# SCH_Driver_RL.net
KiCad netlist of a schematic drawn in Altium Designer
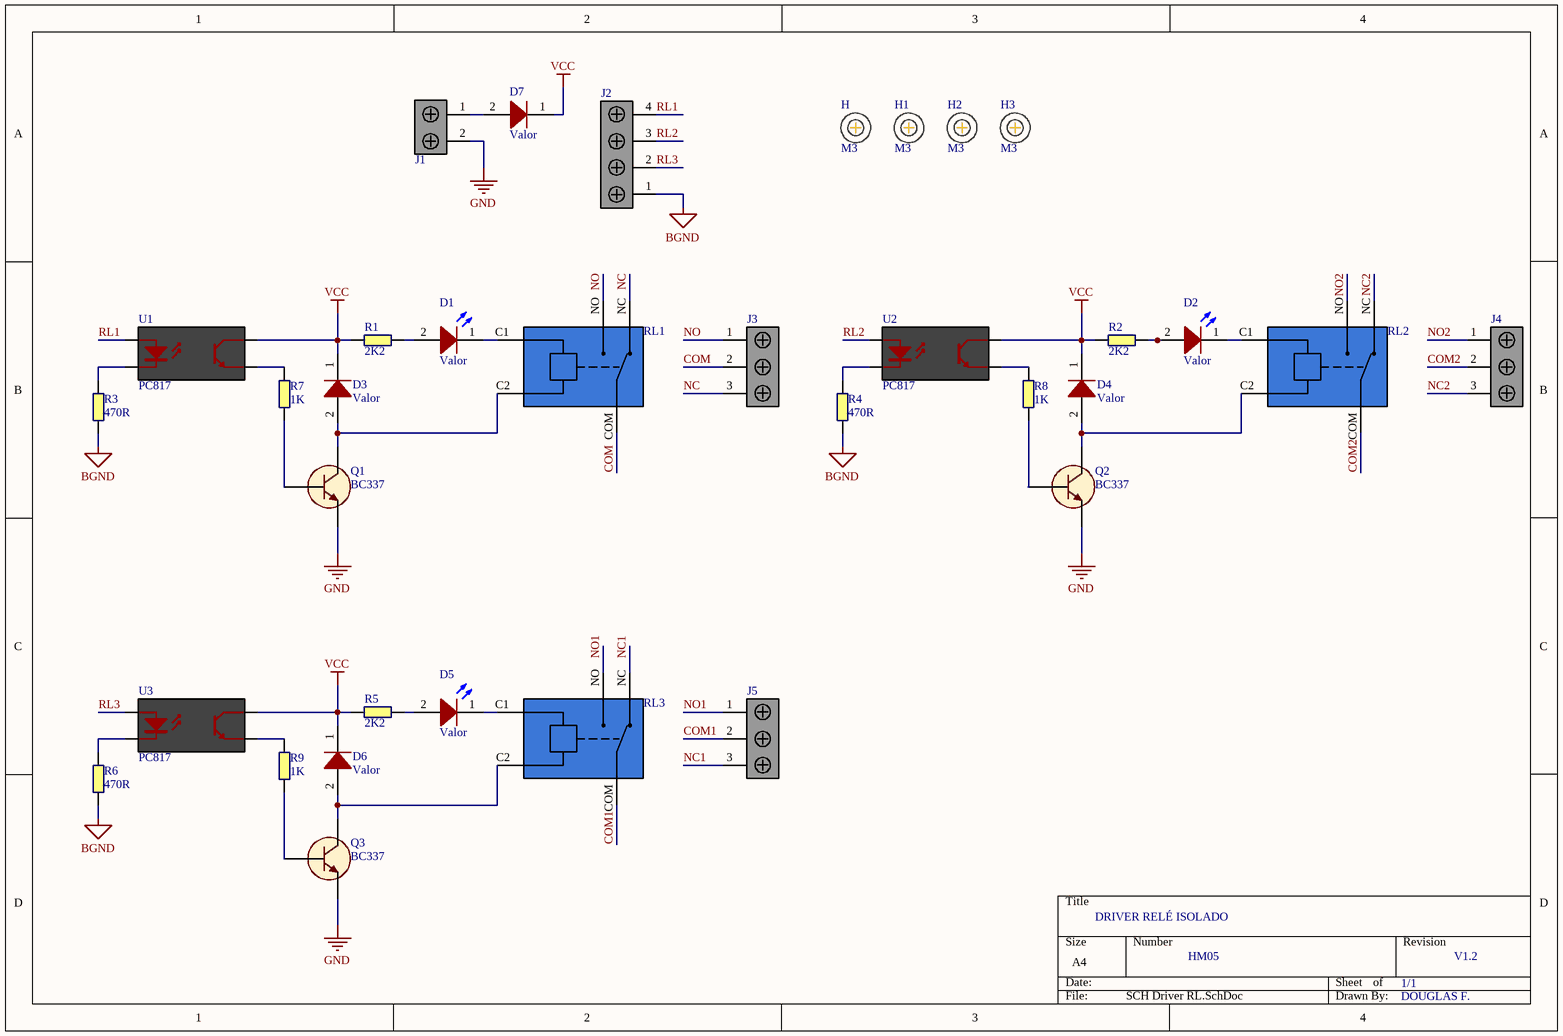
[diagram p0: SCH Driver RL.SchDoc]

(export (version "E")
  (design (tool "Eeschema 10.0.6"))
  (components
    (comp (ref "D1")
      (value "Valor")
      (footprint "LED 3MM")
      (description "Typical RED, GREEN, YELLOW, AMBER GaAs LED")
      (fields (field (name "PUBLISHER") "Altium Limited"))
      (libsource (lib "Driver relé") (part "LED"))
    )
    (comp (ref "D2")
      (value "Valor")
      (footprint "LED 3MM")
      (description "Typical RED, GREEN, YELLOW, AMBER GaAs LED")
      (fields (field (name "PUBLISHER") "Altium Limited"))
      (libsource (lib "Driver relé") (part "LED"))
    )
    (comp (ref "D3")
      (value "Valor")
      (footprint "1N4148 DO-35")
      (description "Diodo rapido")
      (fields (field (name "PUBLISHER") "Altium Limited"))
      (libsource (lib "Driver relé") (part "DIODO 1N4148"))
    )
    (comp (ref "D4")
      (value "Valor")
      (footprint "1N4148 DO-35")
      (description "Diodo rapido")
      (fields (field (name "PUBLISHER") "Altium Limited"))
      (libsource (lib "Driver relé") (part "DIODO 1N4148"))
    )
    (comp (ref "D5")
      (value "Valor")
      (footprint "LED 3MM")
      (description "Typical RED, GREEN, YELLOW, AMBER GaAs LED")
      (fields (field (name "PUBLISHER") "Altium Limited"))
      (libsource (lib "Driver relé") (part "LED"))
    )
    (comp (ref "D6")
      (value "Valor")
      (footprint "1N4148 DO-35")
      (description "Diodo rapido")
      (fields (field (name "PUBLISHER") "Altium Limited"))
      (libsource (lib "Driver relé") (part "DIODO 1N4148"))
    )
    (comp (ref "D7")
      (value "Valor")
      (footprint "1N4007 DO-41")
      (description "Diodo rapido")
      (fields (field (name "PUBLISHER") "Altium Limited"))
      (libsource (lib "Driver relé") (part "DIODO 1N4007"))
    )
    (comp (ref "H") (value "M3") (footprint "Parafuso M3") (libsource (lib "Driver relé") (part "Furo M3")))
    (comp (ref "H1") (value "M3") (footprint "Parafuso M3") (libsource (lib "Driver relé") (part "Furo M3")))
    (comp (ref "H2") (value "M3") (footprint "Parafuso M3") (libsource (lib "Driver relé") (part "Furo M3")))
    (comp (ref "H3") (value "M3") (footprint "Parafuso M3") (libsource (lib "Driver relé") (part "Furo M3")))
    (comp (ref "J1")
      (value "Conector 2v Phoenix")
      (footprint "Terminal block 5mm 2V")
      (description "Block, Terminal; 6 A; 63 V; 5 mm; 26 to 20 AWG; 2; Screw; Soldering; 1.5 kV")
      (fields
        (field (name "MANUFACTURER") "Phoenix Contact")
        (field (name "MANUFACTURER PART NUMBER") "1725656")
      )
      (libsource (lib "Driver relé") (part "TERMINAL BLOCK 2V"))
    )
    (comp (ref "J2")
      (value "TERMINAL BLOCK 4V")
      (footprint "Terminal block 5mm 4V")
      (description "Block, Terminal; 6 A; 63 V; 5 mm; 26 to 20 AWG; 4 Screw; Soldering; 1.5 kV")
      (libsource (lib "Driver relé") (part "TERMINAL BLOCK 4V"))
    )
    (comp (ref "J3")
      (value "Conector 2v Phoenix")
      (footprint "Terminal block 5mm 3V")
      (description "Block, Terminal; 6 A; 63 V; 5 mm; 26 to 20 AWG; 3; Screw; Soldering; 1.5 kV")
      (fields
        (field (name "MANUFACTURER") "Phoenix Contact")
        (field (name "MANUFACTURER PART NUMBER") "1725656")
      )
      (libsource (lib "Driver relé") (part "TERMINAL BLOCK 3V"))
    )
    (comp (ref "J4")
      (value "Conector 2v Phoenix")
      (footprint "Terminal block 5mm 3V")
      (description "Block, Terminal; 6 A; 63 V; 5 mm; 26 to 20 AWG; 3; Screw; Soldering; 1.5 kV")
      (fields
        (field (name "MANUFACTURER") "Phoenix Contact")
        (field (name "MANUFACTURER PART NUMBER") "1725656")
      )
      (libsource (lib "Driver relé") (part "TERMINAL BLOCK 3V"))
    )
    (comp (ref "J5")
      (value "Conector 2v Phoenix")
      (footprint "Terminal block 5mm 3V")
      (description "Block, Terminal; 6 A; 63 V; 5 mm; 26 to 20 AWG; 3; Screw; Soldering; 1.5 kV")
      (fields
        (field (name "MANUFACTURER") "Phoenix Contact")
        (field (name "MANUFACTURER PART NUMBER") "1725656")
      )
      (libsource (lib "Driver relé") (part "TERMINAL BLOCK 3V"))
    )
    (comp (ref "Q1") (value "BC337") (footprint "TO 92") (libsource (lib "Driver relé") (part "BC337")))
    (comp (ref "Q2") (value "BC337") (footprint "TO 92") (libsource (lib "Driver relé") (part "BC337")))
    (comp (ref "Q3") (value "BC337") (footprint "TO 92") (libsource (lib "Driver relé") (part "BC337")))
    (comp (ref "R1")
      (value "2K2")
      (footprint "RES 1/4 PTH")
      (description "Resistor")
      (fields (field (name "PUBLISHER") "Altium Limited"))
      (libsource (lib "Driver relé") (part "RESISTOR 1/4W"))
    )
    (comp (ref "R2")
      (value "2K2")
      (footprint "RES 1/4 PTH")
      (description "Resistor")
      (fields (field (name "PUBLISHER") "Altium Limited"))
      (libsource (lib "Driver relé") (part "RESISTOR 1/4W"))
    )
    (comp (ref "R3")
      (value "470R")
      (footprint "RES 1/4 PTH")
      (description "Resistor")
      (fields (field (name "PUBLISHER") "Altium Limited"))
      (libsource (lib "") (part "RESISTOR 1/4W_1"))
    )
    (comp (ref "R4")
      (value "470R")
      (footprint "RES 1/4 PTH")
      (description "Resistor")
      (fields (field (name "PUBLISHER") "Altium Limited"))
      (libsource (lib "") (part "RESISTOR 1/4W_1"))
    )
    (comp (ref "R5")
      (value "2K2")
      (footprint "RES 1/4 PTH")
      (description "Resistor")
      (fields (field (name "PUBLISHER") "Altium Limited"))
      (libsource (lib "Driver relé") (part "RESISTOR 1/4W"))
    )
    (comp (ref "R6")
      (value "470R")
      (footprint "RES 1/4 PTH")
      (description "Resistor")
      (fields (field (name "PUBLISHER") "Altium Limited"))
      (libsource (lib "") (part "RESISTOR 1/4W_1"))
    )
    (comp (ref "R7")
      (value "1K")
      (footprint "RES 1/4 PTH")
      (description "Resistor")
      (fields (field (name "PUBLISHER") "Altium Limited"))
      (libsource (lib "") (part "RESISTOR 1/4W_1"))
    )
    (comp (ref "R8")
      (value "1K")
      (footprint "RES 1/4 PTH")
      (description "Resistor")
      (fields (field (name "PUBLISHER") "Altium Limited"))
      (libsource (lib "") (part "RESISTOR 1/4W_1"))
    )
    (comp (ref "R9")
      (value "1K")
      (footprint "RES 1/4 PTH")
      (description "Resistor")
      (fields (field (name "PUBLISHER") "Altium Limited"))
      (libsource (lib "") (part "RESISTOR 1/4W_1"))
    )
    (comp (ref "RL1")
      (value "Relé 12v 5p")
      (footprint "RELAY")
      (libsource (lib "Driver relé") (part "Relé 12v 5p"))
    )
    (comp (ref "RL2")
      (value "Relé 12v 5p")
      (footprint "RELAY")
      (libsource (lib "Driver relé") (part "Relé 12v 5p"))
    )
    (comp (ref "RL3")
      (value "Relé 12v 5p")
      (footprint "RELAY")
      (libsource (lib "Driver relé") (part "Relé 12v 5p"))
    )
    (comp (ref "U1") (value "PC817") (footprint "PC817 DIP-4") (libsource (lib "Driver relé") (part "PC817")))
    (comp (ref "U2") (value "PC817") (footprint "PC817 DIP-4") (libsource (lib "Driver relé") (part "PC817")))
    (comp (ref "U3") (value "PC817") (footprint "PC817 DIP-4") (libsource (lib "Driver relé") (part "PC817")))
  )
  (nets
    (net (code "1") (name "/COM") (class "Default")
      (node (ref "J3") (pin "2") (pinfunction "2_2") (pintype "passive"))
      (node (ref "RL1") (pin "COM") (pinfunction "COM_COM") (pintype "passive"))
    )
    (net (code "2") (name "/COM1") (class "Default")
      (node (ref "J5") (pin "2") (pinfunction "2_2") (pintype "passive"))
      (node (ref "RL3") (pin "COM") (pinfunction "COM_COM") (pintype "passive"))
    )
    (net (code "3") (name "/COM2") (class "Default")
      (node (ref "J4") (pin "2") (pinfunction "2_2") (pintype "passive"))
      (node (ref "RL2") (pin "COM") (pinfunction "COM_COM") (pintype "passive"))
    )
    (net (code "4") (name "/NC") (class "Default")
      (node (ref "J3") (pin "3") (pinfunction "3_3") (pintype "passive"))
      (node (ref "RL1") (pin "NC") (pinfunction "NC_NC") (pintype "passive"))
    )
    (net (code "5") (name "/NC1") (class "Default")
      (node (ref "J5") (pin "3") (pinfunction "3_3") (pintype "passive"))
      (node (ref "RL3") (pin "NC") (pinfunction "NC_NC") (pintype "passive"))
    )
    (net (code "6") (name "/NC2") (class "Default")
      (node (ref "J4") (pin "3") (pinfunction "3_3") (pintype "passive"))
      (node (ref "RL2") (pin "NC") (pinfunction "NC_NC") (pintype "passive"))
    )
    (net (code "7") (name "/NO") (class "Default")
      (node (ref "J3") (pin "1") (pinfunction "1_1") (pintype "passive"))
      (node (ref "RL1") (pin "NO") (pinfunction "NO_NO") (pintype "passive"))
    )
    (net (code "8") (name "/NO1") (class "Default")
      (node (ref "J5") (pin "1") (pinfunction "1_1") (pintype "passive"))
      (node (ref "RL3") (pin "NO") (pinfunction "NO_NO") (pintype "passive"))
    )
    (net (code "9") (name "/NO2") (class "Default")
      (node (ref "J4") (pin "1") (pinfunction "1_1") (pintype "passive"))
      (node (ref "RL2") (pin "NO") (pinfunction "NO_NO") (pintype "passive"))
    )
    (net (code "10") (name "/RL1") (class "Default")
      (node (ref "J2") (pin "4") (pinfunction "4_4") (pintype "passive"))
      (node (ref "U1") (pin "1") (pinfunction "A_1") (pintype "passive"))
    )
    (net (code "11") (name "/RL2") (class "Default")
      (node (ref "J2") (pin "3") (pinfunction "3_3") (pintype "passive"))
      (node (ref "U2") (pin "1") (pinfunction "A_1") (pintype "passive"))
    )
    (net (code "12") (name "/RL3") (class "Default")
      (node (ref "J2") (pin "2") (pinfunction "2_2") (pintype "passive"))
      (node (ref "U3") (pin "1") (pinfunction "A_1") (pintype "passive"))
    )
    (net (code "13") (name "BGND") (class "Default")
      (node (ref "J2") (pin "1") (pinfunction "1_1") (pintype "passive"))
      (node (ref "R3") (pin "1") (pinfunction "1_1") (pintype "passive"))
      (node (ref "R4") (pin "1") (pinfunction "1_1") (pintype "passive"))
      (node (ref "R6") (pin "1") (pinfunction "1_1") (pintype "passive"))
    )
    (net (code "14") (name "GND") (class "Default")
      (node (ref "J1") (pin "2") (pinfunction "2_2") (pintype "passive"))
      (node (ref "Q1") (pin "3") (pinfunction "E_3") (pintype "passive"))
      (node (ref "Q2") (pin "3") (pinfunction "E_3") (pintype "passive"))
      (node (ref "Q3") (pin "3") (pinfunction "E_3") (pintype "passive"))
    )
    (net (code "15") (name "Net-(D1-1)") (class "Default")
      (node (ref "D1") (pin "2") (pinfunction "1_2") (pintype "passive"))
      (node (ref "R1") (pin "1") (pinfunction "1_1") (pintype "passive"))
    )
    (net (code "16") (name "Net-(D1-2)") (class "Default")
      (node (ref "D1") (pin "1") (pinfunction "2_1") (pintype "passive"))
      (node (ref "RL1") (pin "C1") (pinfunction "COIL_1_C1") (pintype "passive"))
    )
    (net (code "17") (name "Net-(D2-1)") (class "Default")
      (node (ref "D2") (pin "2") (pinfunction "1_2") (pintype "passive"))
      (node (ref "R2") (pin "1") (pinfunction "1_1") (pintype "passive"))
    )
    (net (code "18") (name "Net-(D2-2)") (class "Default")
      (node (ref "D2") (pin "1") (pinfunction "2_1") (pintype "passive"))
      (node (ref "RL2") (pin "C1") (pinfunction "COIL_1_C1") (pintype "passive"))
    )
    (net (code "19") (name "Net-(D5-1)") (class "Default")
      (node (ref "D5") (pin "2") (pinfunction "1_2") (pintype "passive"))
      (node (ref "R5") (pin "1") (pinfunction "1_1") (pintype "passive"))
    )
    (net (code "20") (name "Net-(D5-2)") (class "Default")
      (node (ref "D5") (pin "1") (pinfunction "2_1") (pintype "passive"))
      (node (ref "RL3") (pin "C1") (pinfunction "COIL_1_C1") (pintype "passive"))
    )
    (net (code "21") (name "Net-(D7-Pad2)") (class "Default")
      (node (ref "D7") (pin "2") (pinfunction "2_2") (pintype "passive"))
      (node (ref "J1") (pin "1") (pinfunction "1_1") (pintype "passive"))
    )
    (net (code "22") (name "Net-(Q1-B)") (class "Default")
      (node (ref "Q1") (pin "2") (pinfunction "B_2") (pintype "passive"))
      (node (ref "R7") (pin "1") (pinfunction "1_1") (pintype "passive"))
    )
    (net (code "23") (name "Net-(Q1-C)") (class "Default")
      (node (ref "D3") (pin "2") (pinfunction "2_2") (pintype "passive"))
      (node (ref "Q1") (pin "1") (pinfunction "C_1") (pintype "passive"))
      (node (ref "RL1") (pin "C2") (pinfunction "COIL_2_C2") (pintype "passive"))
    )
    (net (code "24") (name "Net-(Q2-B)") (class "Default")
      (node (ref "Q2") (pin "2") (pinfunction "B_2") (pintype "passive"))
      (node (ref "R8") (pin "1") (pinfunction "1_1") (pintype "passive"))
    )
    (net (code "25") (name "Net-(Q2-C)") (class "Default")
      (node (ref "D4") (pin "2") (pinfunction "2_2") (pintype "passive"))
      (node (ref "Q2") (pin "1") (pinfunction "C_1") (pintype "passive"))
      (node (ref "RL2") (pin "C2") (pinfunction "COIL_2_C2") (pintype "passive"))
    )
    (net (code "26") (name "Net-(Q3-B)") (class "Default")
      (node (ref "Q3") (pin "2") (pinfunction "B_2") (pintype "passive"))
      (node (ref "R9") (pin "1") (pinfunction "1_1") (pintype "passive"))
    )
    (net (code "27") (name "Net-(Q3-C)") (class "Default")
      (node (ref "D6") (pin "2") (pinfunction "2_2") (pintype "passive"))
      (node (ref "Q3") (pin "1") (pinfunction "C_1") (pintype "passive"))
      (node (ref "RL3") (pin "C2") (pinfunction "COIL_2_C2") (pintype "passive"))
    )
    (net (code "28") (name "Net-(U1-E)") (class "Default")
      (node (ref "R7") (pin "2") (pinfunction "2_2") (pintype "passive"))
      (node (ref "U1") (pin "3") (pinfunction "E_3") (pintype "passive"))
    )
    (net (code "29") (name "Net-(U1-K)") (class "Default")
      (node (ref "R3") (pin "2") (pinfunction "2_2") (pintype "passive"))
      (node (ref "U1") (pin "2") (pinfunction "K_2") (pintype "passive"))
    )
    (net (code "30") (name "Net-(U2-E)") (class "Default")
      (node (ref "R8") (pin "2") (pinfunction "2_2") (pintype "passive"))
      (node (ref "U2") (pin "3") (pinfunction "E_3") (pintype "passive"))
    )
    (net (code "31") (name "Net-(U2-K)") (class "Default")
      (node (ref "R4") (pin "2") (pinfunction "2_2") (pintype "passive"))
      (node (ref "U2") (pin "2") (pinfunction "K_2") (pintype "passive"))
    )
    (net (code "32") (name "Net-(U3-E)") (class "Default")
      (node (ref "R9") (pin "2") (pinfunction "2_2") (pintype "passive"))
      (node (ref "U3") (pin "3") (pinfunction "E_3") (pintype "passive"))
    )
    (net (code "33") (name "Net-(U3-K)") (class "Default")
      (node (ref "R6") (pin "2") (pinfunction "2_2") (pintype "passive"))
      (node (ref "U3") (pin "2") (pinfunction "K_2") (pintype "passive"))
    )
    (net (code "34") (name "VCC") (class "Default")
      (node (ref "D3") (pin "1") (pinfunction "1_1") (pintype "passive"))
      (node (ref "D4") (pin "1") (pinfunction "1_1") (pintype "passive"))
      (node (ref "D6") (pin "1") (pinfunction "1_1") (pintype "passive"))
      (node (ref "D7") (pin "1") (pinfunction "1_1") (pintype "passive"))
      (node (ref "R1") (pin "2") (pinfunction "2_2") (pintype "passive"))
      (node (ref "R2") (pin "2") (pinfunction "2_2") (pintype "passive"))
      (node (ref "R5") (pin "2") (pinfunction "2_2") (pintype "passive"))
      (node (ref "U1") (pin "4") (pinfunction "C_4") (pintype "passive"))
      (node (ref "U2") (pin "4") (pinfunction "C_4") (pintype "passive"))
      (node (ref "U3") (pin "4") (pinfunction "C_4") (pintype "passive"))
    )
  )
)
